# clock.net
KiCad netlist of a schematic drawn in EAGLE
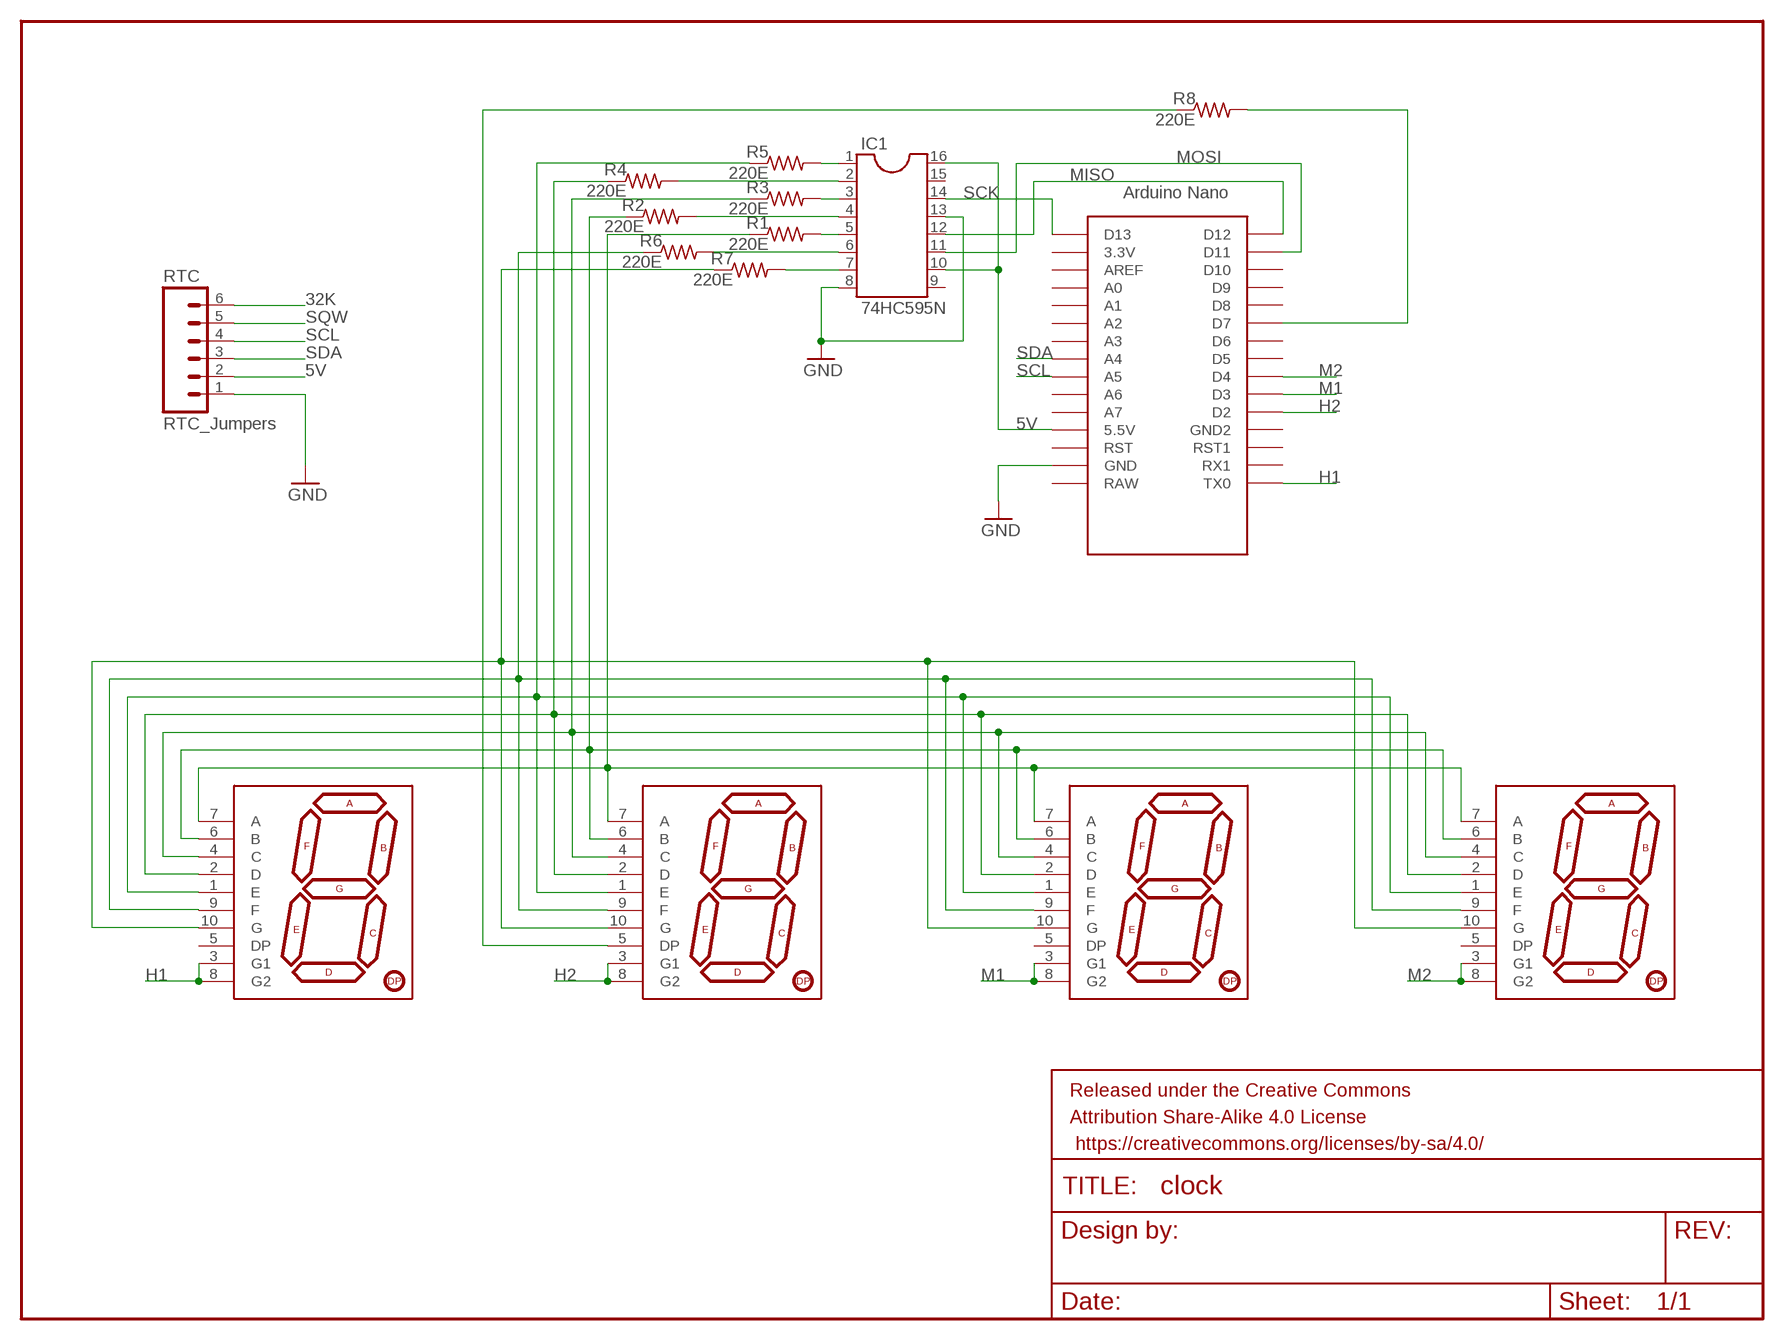
[diagram p0: schematic, sheet 1]

(export (version "E")
  (design (tool "Eeschema 10.0.6"))
  (components
    (comp (ref "FRAME1")
      (value "FRAME-LETTERNO_PACKAGE")
      (footprint "eagle-import:DUMMY")
      (fields (field (name "DESIGNER") "Nobody"))
      (libsource (lib "eagle-import") (part "FRAME-LETTERNO_PACKAGE"))
    )
    (comp (ref "IC1")
      (value "74HC595N")
      (footprint "eagle-import:DIL16")
      (libsource (lib "eagle-import") (part "DIL16"))
    )
    (comp (ref "R1")
      (value "220E")
      (footprint "eagle-import:0309_10")
      (libsource (lib "eagle-import") (part "R-US_0309/10"))
    )
    (comp (ref "R2")
      (value "220E")
      (footprint "eagle-import:0309_10")
      (libsource (lib "eagle-import") (part "R-US_0309/10"))
    )
    (comp (ref "R3")
      (value "220E")
      (footprint "eagle-import:0309_10")
      (libsource (lib "eagle-import") (part "R-US_0309/10"))
    )
    (comp (ref "R4")
      (value "220E")
      (footprint "eagle-import:0309_10")
      (libsource (lib "eagle-import") (part "R-US_0309/10"))
    )
    (comp (ref "R5")
      (value "220E")
      (footprint "eagle-import:0309_10")
      (libsource (lib "eagle-import") (part "R-US_0309/10"))
    )
    (comp (ref "R6")
      (value "220E")
      (footprint "eagle-import:0309_10")
      (libsource (lib "eagle-import") (part "R-US_0309/10"))
    )
    (comp (ref "R7")
      (value "220E")
      (footprint "eagle-import:0309_10")
      (libsource (lib "eagle-import") (part "R-US_0309/10"))
    )
    (comp (ref "R8")
      (value "220E")
      (footprint "eagle-import:0309_10")
      (libsource (lib "eagle-import") (part "R-US_0309/10"))
    )
    (comp (ref "RTC")
      (value "RTC_Jumpers")
      (footprint "eagle-import:1X06")
      (libsource (lib "eagle-import") (part "M06SIP"))
    )
    (comp (ref "U$1")
      (value "7-SEGMENT-1INCH-DIGIT-RED")
      (footprint "eagle-import:7-SEGMENT-1_PTH")
      (libsource (lib "eagle-import") (part "7-SEGMENT-1INCH-DIGIT-RED"))
    )
    (comp (ref "U$2")
      (value "7-SEGMENT-1INCH-DIGIT-RED")
      (footprint "eagle-import:7-SEGMENT-1_PTH")
      (libsource (lib "eagle-import") (part "7-SEGMENT-1INCH-DIGIT-RED"))
    )
    (comp (ref "U$3")
      (value "7-SEGMENT-1INCH-DIGIT-RED")
      (footprint "eagle-import:7-SEGMENT-1_PTH")
      (libsource (lib "eagle-import") (part "7-SEGMENT-1INCH-DIGIT-RED"))
    )
    (comp (ref "U$4")
      (value "7-SEGMENT-1INCH-DIGIT-RED")
      (footprint "eagle-import:7-SEGMENT-1_PTH")
      (libsource (lib "eagle-import") (part "7-SEGMENT-1INCH-DIGIT-RED"))
    )
    (comp (ref "U$5")
      (value "NANO")
      (footprint "eagle-import:NANO")
      (libsource (lib "eagle-import") (part "NANO"))
    )
  )
  (nets
    (net (code "1") (name "/5V") (class "Default")
      (node (ref "IC1") (pin "10") (pinfunction "10_10") (pintype "passive"))
      (node (ref "IC1") (pin "16") (pinfunction "16_16") (pintype "passive"))
      (node (ref "RTC") (pin "2") (pinfunction "2_2") (pintype "passive"))
      (node (ref "U$5") (pin "5V") (pinfunction "5.5V_5V") (pintype "bidirectional"))
    )
    (net (code "2") (name "/32K") (class "Default")
      (node (ref "RTC") (pin "6") (pinfunction "6_6") (pintype "passive"))
    )
    (net (code "3") (name "/H1") (class "Default")
      (node (ref "U$1") (pin "3") (pinfunction "G1_3") (pintype "bidirectional"))
      (node (ref "U$1") (pin "8") (pinfunction "G2_8") (pintype "bidirectional"))
      (node (ref "U$5") (pin "TX0") (pinfunction "TX0_TX0") (pintype "bidirectional"))
    )
    (net (code "4") (name "/H2") (class "Default")
      (node (ref "U$2") (pin "3") (pinfunction "G1_3") (pintype "bidirectional"))
      (node (ref "U$2") (pin "8") (pinfunction "G2_8") (pintype "bidirectional"))
      (node (ref "U$5") (pin "D2") (pinfunction "D2_D2") (pintype "bidirectional"))
    )
    (net (code "5") (name "/M1") (class "Default")
      (node (ref "U$3") (pin "3") (pinfunction "G1_3") (pintype "bidirectional"))
      (node (ref "U$3") (pin "8") (pinfunction "G2_8") (pintype "bidirectional"))
      (node (ref "U$5") (pin "D3") (pinfunction "D3_D3") (pintype "bidirectional"))
    )
    (net (code "6") (name "/M2") (class "Default")
      (node (ref "U$4") (pin "3") (pinfunction "G1_3") (pintype "bidirectional"))
      (node (ref "U$4") (pin "8") (pinfunction "G2_8") (pintype "bidirectional"))
      (node (ref "U$5") (pin "D4") (pinfunction "D4_D4") (pintype "bidirectional"))
    )
    (net (code "7") (name "/MISO") (class "Default")
      (node (ref "IC1") (pin "12") (pinfunction "12_12") (pintype "passive"))
      (node (ref "U$5") (pin "D12") (pinfunction "D12_D12") (pintype "bidirectional"))
    )
    (net (code "8") (name "/MOSI") (class "Default")
      (node (ref "IC1") (pin "11") (pinfunction "11_11") (pintype "passive"))
      (node (ref "U$5") (pin "D11") (pinfunction "D11_D11") (pintype "bidirectional"))
    )
    (net (code "9") (name "/SCK") (class "Default")
      (node (ref "IC1") (pin "14") (pinfunction "14_14") (pintype "passive"))
      (node (ref "U$5") (pin "D13") (pinfunction "D13_D13") (pintype "bidirectional"))
    )
    (net (code "10") (name "/SCL") (class "Default")
      (node (ref "RTC") (pin "4") (pinfunction "4_4") (pintype "passive"))
      (node (ref "U$5") (pin "A5") (pinfunction "A5_A5") (pintype "bidirectional"))
    )
    (net (code "11") (name "/SDA") (class "Default")
      (node (ref "RTC") (pin "3") (pinfunction "3_3") (pintype "passive"))
      (node (ref "U$5") (pin "A4") (pinfunction "A4_A4") (pintype "bidirectional"))
    )
    (net (code "12") (name "/SQW") (class "Default")
      (node (ref "RTC") (pin "5") (pinfunction "5_5") (pintype "passive"))
    )
    (net (code "13") (name "GND") (class "Default")
      (node (ref "IC1") (pin "13") (pinfunction "13_13") (pintype "passive"))
      (node (ref "IC1") (pin "8") (pinfunction "8_8") (pintype "passive"))
      (node (ref "RTC") (pin "1") (pinfunction "1_1") (pintype "passive"))
      (node (ref "U$5") (pin "GND") (pinfunction "GND_GND") (pintype "bidirectional"))
    )
    (net (code "14") (name "Net-(IC1-Pad1)") (class "Default")
      (node (ref "IC1") (pin "1") (pinfunction "1_1") (pintype "passive"))
      (node (ref "R5") (pin "2") (pinfunction "2_2") (pintype "passive"))
    )
    (net (code "15") (name "Net-(IC1-Pad2)") (class "Default")
      (node (ref "IC1") (pin "2") (pinfunction "2_2") (pintype "passive"))
      (node (ref "R4") (pin "2") (pinfunction "2_2") (pintype "passive"))
    )
    (net (code "16") (name "Net-(IC1-Pad3)") (class "Default")
      (node (ref "IC1") (pin "3") (pinfunction "3_3") (pintype "passive"))
      (node (ref "R3") (pin "2") (pinfunction "2_2") (pintype "passive"))
    )
    (net (code "17") (name "Net-(IC1-Pad4)") (class "Default")
      (node (ref "IC1") (pin "4") (pinfunction "4_4") (pintype "passive"))
      (node (ref "R2") (pin "2") (pinfunction "2_2") (pintype "passive"))
    )
    (net (code "18") (name "Net-(IC1-Pad5)") (class "Default")
      (node (ref "IC1") (pin "5") (pinfunction "5_5") (pintype "passive"))
      (node (ref "R1") (pin "2") (pinfunction "2_2") (pintype "passive"))
    )
    (net (code "19") (name "Net-(IC1-Pad6)") (class "Default")
      (node (ref "IC1") (pin "6") (pinfunction "6_6") (pintype "passive"))
      (node (ref "R6") (pin "2") (pinfunction "2_2") (pintype "passive"))
    )
    (net (code "20") (name "Net-(IC1-Pad7)") (class "Default")
      (node (ref "IC1") (pin "7") (pinfunction "7_7") (pintype "passive"))
      (node (ref "R7") (pin "2") (pinfunction "2_2") (pintype "passive"))
    )
    (net (code "21") (name "Net-(R8-Pad2)") (class "Default")
      (node (ref "R8") (pin "2") (pinfunction "2_2") (pintype "passive"))
      (node (ref "U$5") (pin "D7") (pinfunction "D7_D7") (pintype "bidirectional"))
    )
    (net (code "22") (name "Net-(U$1-A)") (class "Default")
      (node (ref "R1") (pin "1") (pinfunction "1_1") (pintype "passive"))
      (node (ref "U$1") (pin "7") (pinfunction "A_7") (pintype "bidirectional"))
      (node (ref "U$2") (pin "7") (pinfunction "A_7") (pintype "bidirectional"))
      (node (ref "U$3") (pin "7") (pinfunction "A_7") (pintype "bidirectional"))
      (node (ref "U$4") (pin "7") (pinfunction "A_7") (pintype "bidirectional"))
    )
    (net (code "23") (name "Net-(U$1-B)") (class "Default")
      (node (ref "R2") (pin "1") (pinfunction "1_1") (pintype "passive"))
      (node (ref "U$1") (pin "6") (pinfunction "B_6") (pintype "bidirectional"))
      (node (ref "U$2") (pin "6") (pinfunction "B_6") (pintype "bidirectional"))
      (node (ref "U$3") (pin "6") (pinfunction "B_6") (pintype "bidirectional"))
      (node (ref "U$4") (pin "6") (pinfunction "B_6") (pintype "bidirectional"))
    )
    (net (code "24") (name "Net-(U$1-C)") (class "Default")
      (node (ref "R3") (pin "1") (pinfunction "1_1") (pintype "passive"))
      (node (ref "U$1") (pin "4") (pinfunction "C_4") (pintype "bidirectional"))
      (node (ref "U$2") (pin "4") (pinfunction "C_4") (pintype "bidirectional"))
      (node (ref "U$3") (pin "4") (pinfunction "C_4") (pintype "bidirectional"))
      (node (ref "U$4") (pin "4") (pinfunction "C_4") (pintype "bidirectional"))
    )
    (net (code "25") (name "Net-(U$1-D)") (class "Default")
      (node (ref "R4") (pin "1") (pinfunction "1_1") (pintype "passive"))
      (node (ref "U$1") (pin "2") (pinfunction "D_2") (pintype "bidirectional"))
      (node (ref "U$2") (pin "2") (pinfunction "D_2") (pintype "bidirectional"))
      (node (ref "U$3") (pin "2") (pinfunction "D_2") (pintype "bidirectional"))
      (node (ref "U$4") (pin "2") (pinfunction "D_2") (pintype "bidirectional"))
    )
    (net (code "26") (name "Net-(U$1-E)") (class "Default")
      (node (ref "R5") (pin "1") (pinfunction "1_1") (pintype "passive"))
      (node (ref "U$1") (pin "1") (pinfunction "E_1") (pintype "bidirectional"))
      (node (ref "U$2") (pin "1") (pinfunction "E_1") (pintype "bidirectional"))
      (node (ref "U$3") (pin "1") (pinfunction "E_1") (pintype "bidirectional"))
      (node (ref "U$4") (pin "1") (pinfunction "E_1") (pintype "bidirectional"))
    )
    (net (code "27") (name "Net-(U$1-F)") (class "Default")
      (node (ref "R6") (pin "1") (pinfunction "1_1") (pintype "passive"))
      (node (ref "U$1") (pin "9") (pinfunction "F_9") (pintype "bidirectional"))
      (node (ref "U$2") (pin "9") (pinfunction "F_9") (pintype "bidirectional"))
      (node (ref "U$3") (pin "9") (pinfunction "F_9") (pintype "bidirectional"))
      (node (ref "U$4") (pin "9") (pinfunction "F_9") (pintype "bidirectional"))
    )
    (net (code "28") (name "Net-(U$1-G)") (class "Default")
      (node (ref "R7") (pin "1") (pinfunction "1_1") (pintype "passive"))
      (node (ref "U$1") (pin "10") (pinfunction "G_10") (pintype "bidirectional"))
      (node (ref "U$2") (pin "10") (pinfunction "G_10") (pintype "bidirectional"))
      (node (ref "U$3") (pin "10") (pinfunction "G_10") (pintype "bidirectional"))
      (node (ref "U$4") (pin "10") (pinfunction "G_10") (pintype "bidirectional"))
    )
    (net (code "29") (name "Net-(U$2-DP)") (class "Default")
      (node (ref "R8") (pin "1") (pinfunction "1_1") (pintype "passive"))
      (node (ref "U$2") (pin "5") (pinfunction "DP_5") (pintype "bidirectional"))
    )
    (net (code "30") (name "unconnected-(IC1-Pad9)") (class "Default")
      (node (ref "IC1") (pin "9") (pinfunction "9_9") (pintype "passive"))
    )
    (net (code "31") (name "unconnected-(IC1-Pad15)") (class "Default")
      (node (ref "IC1") (pin "15") (pinfunction "15_15") (pintype "passive"))
    )
    (net (code "32") (name "unconnected-(U$1-DP-Pad5)") (class "Default")
      (node (ref "U$1") (pin "5") (pinfunction "DP_5") (pintype "bidirectional"))
    )
    (net (code "33") (name "unconnected-(U$3-DP-Pad5)") (class "Default")
      (node (ref "U$3") (pin "5") (pinfunction "DP_5") (pintype "bidirectional"))
    )
    (net (code "34") (name "unconnected-(U$4-DP-Pad5)") (class "Default")
      (node (ref "U$4") (pin "5") (pinfunction "DP_5") (pintype "bidirectional"))
    )
    (net (code "35") (name "unconnected-(U$5-GND2-PadGND1)") (class "Default")
      (node (ref "U$5") (pin "GND1") (pinfunction "GND2_GND1") (pintype "bidirectional"))
    )
    (net (code "36") (name "unconnected-(U$5-Pad3.3V)") (class "Default")
      (node (ref "U$5") (pin "3.3V") (pinfunction "3.3V_3.3V") (pintype "bidirectional"))
    )
    (net (code "37") (name "unconnected-(U$5-PadA0)") (class "Default")
      (node (ref "U$5") (pin "A0") (pinfunction "A0_A0") (pintype "bidirectional"))
    )
    (net (code "38") (name "unconnected-(U$5-PadA1)") (class "Default")
      (node (ref "U$5") (pin "A1") (pinfunction "A1_A1") (pintype "bidirectional"))
    )
    (net (code "39") (name "unconnected-(U$5-PadA2)") (class "Default")
      (node (ref "U$5") (pin "A2") (pinfunction "A2_A2") (pintype "bidirectional"))
    )
    (net (code "40") (name "unconnected-(U$5-PadA3)") (class "Default")
      (node (ref "U$5") (pin "A3") (pinfunction "A3_A3") (pintype "bidirectional"))
    )
    (net (code "41") (name "unconnected-(U$5-PadA6)") (class "Default")
      (node (ref "U$5") (pin "A6") (pinfunction "A6_A6") (pintype "bidirectional"))
    )
    (net (code "42") (name "unconnected-(U$5-PadA7)") (class "Default")
      (node (ref "U$5") (pin "A7") (pinfunction "A7_A7") (pintype "bidirectional"))
    )
    (net (code "43") (name "unconnected-(U$5-PadAREF)") (class "Default")
      (node (ref "U$5") (pin "AREF") (pinfunction "AREF_AREF") (pintype "bidirectional"))
    )
    (net (code "44") (name "unconnected-(U$5-PadD5)") (class "Default")
      (node (ref "U$5") (pin "D5") (pinfunction "D5_D5") (pintype "bidirectional"))
    )
    (net (code "45") (name "unconnected-(U$5-PadD6)") (class "Default")
      (node (ref "U$5") (pin "D6") (pinfunction "D6_D6") (pintype "bidirectional"))
    )
    (net (code "46") (name "unconnected-(U$5-PadD8)") (class "Default")
      (node (ref "U$5") (pin "D8") (pinfunction "D8_D8") (pintype "bidirectional"))
    )
    (net (code "47") (name "unconnected-(U$5-PadD9)") (class "Default")
      (node (ref "U$5") (pin "D9") (pinfunction "D9_D9") (pintype "bidirectional"))
    )
    (net (code "48") (name "unconnected-(U$5-PadD10)") (class "Default")
      (node (ref "U$5") (pin "D10") (pinfunction "D10_D10") (pintype "bidirectional"))
    )
    (net (code "49") (name "unconnected-(U$5-PadICSP1)") (class "Default")
      (node (ref "U$5") (pin "ICSP1") (pinfunction "ICSP1_ICSP1") (pintype "bidirectional"))
    )
    (net (code "50") (name "unconnected-(U$5-PadICSP2)") (class "Default")
      (node (ref "U$5") (pin "ICSP2") (pinfunction "ICSP2_ICSP2") (pintype "bidirectional"))
    )
    (net (code "51") (name "unconnected-(U$5-PadICSP3)") (class "Default")
      (node (ref "U$5") (pin "ICSP3") (pinfunction "ICSP3_ICSP3") (pintype "bidirectional"))
    )
    (net (code "52") (name "unconnected-(U$5-PadICSP4)") (class "Default")
      (node (ref "U$5") (pin "ICSP4") (pinfunction "ICSP4_ICSP4") (pintype "bidirectional"))
    )
    (net (code "53") (name "unconnected-(U$5-PadICSP5)") (class "Default")
      (node (ref "U$5") (pin "ICSP5") (pinfunction "ICSP5_ICSP5") (pintype "bidirectional"))
    )
    (net (code "54") (name "unconnected-(U$5-PadICSP6)") (class "Default")
      (node (ref "U$5") (pin "ICSP6") (pinfunction "ICSP6_ICSP6") (pintype "bidirectional"))
    )
    (net (code "55") (name "unconnected-(U$5-PadRAW)") (class "Default")
      (node (ref "U$5") (pin "RAW") (pinfunction "RAW_RAW") (pintype "bidirectional"))
    )
    (net (code "56") (name "unconnected-(U$5-PadRST)") (class "Default")
      (node (ref "U$5") (pin "RST") (pinfunction "RST_RST") (pintype "bidirectional"))
    )
    (net (code "57") (name "unconnected-(U$5-PadRST1)") (class "Default")
      (node (ref "U$5") (pin "RST1") (pinfunction "RST1_RST1") (pintype "bidirectional"))
    )
    (net (code "58") (name "unconnected-(U$5-PadRX1)") (class "Default")
      (node (ref "U$5") (pin "RX1") (pinfunction "RX1_RX1") (pintype "bidirectional"))
    )
  )
)
